# TopLevel.net
KiCad netlist of a schematic drawn in Altium Designer
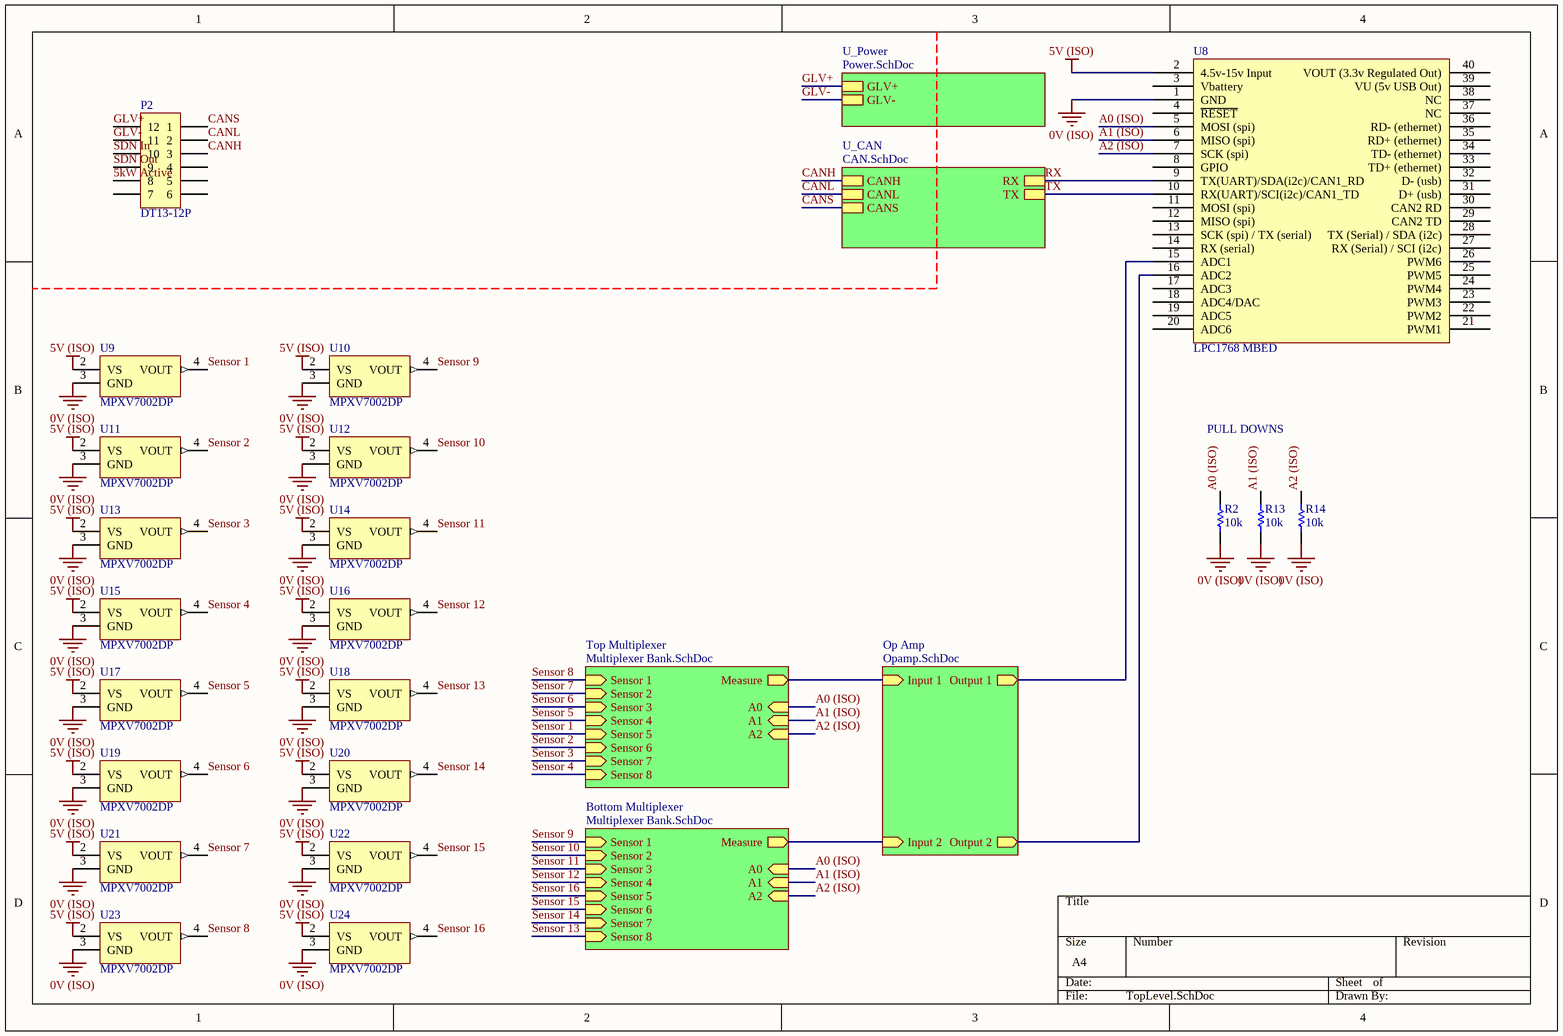
[diagram p0: TopLevel.SchDoc]

(export (version "E")
  (design (tool "Eeschema 10.0.6"))
  (components
    (comp (ref "P2")
      (value "DT13-12P")
      (footprint "DT13-12P")
      (fields (field (name "DIGIKEY PART NUMBER") "1734-1451-ND") (field (name "CONTACT") "Nickel"))
      (libsource (lib "ts_19-standard-connectors") (part "DT13-12P"))
    )
    (comp (ref "R2")
      (value "10k")
      (footprint "0805")
      (fields
        (field (name "MANUFACTURER") "YAGEO")
        (field (name "PART NUMBER") "RC0805FR0710KL")
        (field (name "TOLERANCE") "0.01")
      )
      (libsource (lib "ts_19-standard-library") (part "Resistor"))
    )
    (comp (ref "R13")
      (value "10k")
      (footprint "0805")
      (fields
        (field (name "MANUFACTURER") "YAGEO")
        (field (name "PART NUMBER") "RC0805FR0710KL")
        (field (name "TOLERANCE") "0.01")
      )
      (libsource (lib "ts_19-standard-library") (part "Resistor"))
    )
    (comp (ref "R14")
      (value "10k")
      (footprint "0805")
      (fields
        (field (name "MANUFACTURER") "YAGEO")
        (field (name "PART NUMBER") "RC0805FR0710KL")
        (field (name "TOLERANCE") "0.01")
      )
      (libsource (lib "ts_19-standard-library") (part "Resistor"))
    )
    (comp (ref "U8")
      (value "LPC1768 MBED")
      (footprint "LPC1768 MBED")
      (description "ARM M3 mBed Enabled Microcontroller")
      (fields (field (name "MANUFACTURER") "NXP") (field (name "DIGIKEY PART NUMBER") "568-4916-ND"))
      (libsource (lib "ts_19-standard-library") (part "LPC1768 MBED"))
    )
    (comp (ref "U9")
      (value "MPXV7002DP")
      (footprint "NXP 8-SOP")
      (fields (field (name "MANUFACTURER") "NXP") (field (name "DIGIKEY PART NUMBER") "MPXV7002DP-ND"))
      (libsource (lib "ts_19-standard-library") (part "MPXV7002DP"))
    )
    (comp (ref "U10")
      (value "MPXV7002DP")
      (footprint "NXP 8-SOP")
      (fields (field (name "MANUFACTURER") "NXP") (field (name "DIGIKEY PART NUMBER") "MPXV7002DP-ND"))
      (libsource (lib "ts_19-standard-library") (part "MPXV7002DP"))
    )
    (comp (ref "U11")
      (value "MPXV7002DP")
      (footprint "NXP 8-SOP")
      (fields (field (name "MANUFACTURER") "NXP") (field (name "DIGIKEY PART NUMBER") "MPXV7002DP-ND"))
      (libsource (lib "ts_19-standard-library") (part "MPXV7002DP"))
    )
    (comp (ref "U12")
      (value "MPXV7002DP")
      (footprint "NXP 8-SOP")
      (fields (field (name "MANUFACTURER") "NXP") (field (name "DIGIKEY PART NUMBER") "MPXV7002DP-ND"))
      (libsource (lib "ts_19-standard-library") (part "MPXV7002DP"))
    )
    (comp (ref "U13")
      (value "MPXV7002DP")
      (footprint "NXP 8-SOP")
      (fields (field (name "MANUFACTURER") "NXP") (field (name "DIGIKEY PART NUMBER") "MPXV7002DP-ND"))
      (libsource (lib "ts_19-standard-library") (part "MPXV7002DP"))
    )
    (comp (ref "U14")
      (value "MPXV7002DP")
      (footprint "NXP 8-SOP")
      (fields (field (name "MANUFACTURER") "NXP") (field (name "DIGIKEY PART NUMBER") "MPXV7002DP-ND"))
      (libsource (lib "ts_19-standard-library") (part "MPXV7002DP"))
    )
    (comp (ref "U15")
      (value "MPXV7002DP")
      (footprint "NXP 8-SOP")
      (fields (field (name "MANUFACTURER") "NXP") (field (name "DIGIKEY PART NUMBER") "MPXV7002DP-ND"))
      (libsource (lib "ts_19-standard-library") (part "MPXV7002DP"))
    )
    (comp (ref "U16")
      (value "MPXV7002DP")
      (footprint "NXP 8-SOP")
      (fields (field (name "MANUFACTURER") "NXP") (field (name "DIGIKEY PART NUMBER") "MPXV7002DP-ND"))
      (libsource (lib "ts_19-standard-library") (part "MPXV7002DP"))
    )
    (comp (ref "U17")
      (value "MPXV7002DP")
      (footprint "NXP 8-SOP")
      (fields (field (name "MANUFACTURER") "NXP") (field (name "DIGIKEY PART NUMBER") "MPXV7002DP-ND"))
      (libsource (lib "ts_19-standard-library") (part "MPXV7002DP"))
    )
    (comp (ref "U18")
      (value "MPXV7002DP")
      (footprint "NXP 8-SOP")
      (fields (field (name "MANUFACTURER") "NXP") (field (name "DIGIKEY PART NUMBER") "MPXV7002DP-ND"))
      (libsource (lib "ts_19-standard-library") (part "MPXV7002DP"))
    )
    (comp (ref "U19")
      (value "MPXV7002DP")
      (footprint "NXP 8-SOP")
      (fields (field (name "MANUFACTURER") "NXP") (field (name "DIGIKEY PART NUMBER") "MPXV7002DP-ND"))
      (libsource (lib "ts_19-standard-library") (part "MPXV7002DP"))
    )
    (comp (ref "U20")
      (value "MPXV7002DP")
      (footprint "NXP 8-SOP")
      (fields (field (name "MANUFACTURER") "NXP") (field (name "DIGIKEY PART NUMBER") "MPXV7002DP-ND"))
      (libsource (lib "ts_19-standard-library") (part "MPXV7002DP"))
    )
    (comp (ref "U21")
      (value "MPXV7002DP")
      (footprint "NXP 8-SOP")
      (fields (field (name "MANUFACTURER") "NXP") (field (name "DIGIKEY PART NUMBER") "MPXV7002DP-ND"))
      (libsource (lib "ts_19-standard-library") (part "MPXV7002DP"))
    )
    (comp (ref "U22")
      (value "MPXV7002DP")
      (footprint "NXP 8-SOP")
      (fields (field (name "MANUFACTURER") "NXP") (field (name "DIGIKEY PART NUMBER") "MPXV7002DP-ND"))
      (libsource (lib "ts_19-standard-library") (part "MPXV7002DP"))
    )
    (comp (ref "U23")
      (value "MPXV7002DP")
      (footprint "NXP 8-SOP")
      (fields (field (name "MANUFACTURER") "NXP") (field (name "DIGIKEY PART NUMBER") "MPXV7002DP-ND"))
      (libsource (lib "ts_19-standard-library") (part "MPXV7002DP"))
    )
    (comp (ref "U24")
      (value "MPXV7002DP")
      (footprint "NXP 8-SOP")
      (fields (field (name "MANUFACTURER") "NXP") (field (name "DIGIKEY PART NUMBER") "MPXV7002DP-ND"))
      (libsource (lib "ts_19-standard-library") (part "MPXV7002DP"))
    )
  )
  (nets
    (net (code "1") (name "/5kW Active") (class "Default")
      (node (ref "P2") (pin "8") (pinfunction "8_8") (pintype "passive"))
    )
    (net (code "2") (name "/A0 (ISO)") (class "Default")
      (node (ref "R2") (pin "2") (pinfunction "2_2") (pintype "passive"))
      (node (ref "U8") (pin "5") (pinfunction "MOSI_(spi)_5") (pintype "passive"))
    )
    (net (code "3") (name "/A1 (ISO)") (class "Default")
      (node (ref "R13") (pin "2") (pinfunction "2_2") (pintype "passive"))
      (node (ref "U8") (pin "6") (pinfunction "MISO_(spi)_6") (pintype "passive"))
    )
    (net (code "4") (name "/A2 (ISO)") (class "Default")
      (node (ref "R14") (pin "2") (pinfunction "2_2") (pintype "passive"))
      (node (ref "U8") (pin "7") (pinfunction "SCK_(spi)_7") (pintype "passive"))
    )
    (net (code "5") (name "/CANH") (class "Default")
      (node (ref "P2") (pin "3") (pinfunction "3_3") (pintype "power_in"))
    )
    (net (code "6") (name "/CANL") (class "Default")
      (node (ref "P2") (pin "2") (pinfunction "2_2") (pintype "power_in"))
    )
    (net (code "7") (name "/CANS") (class "Default")
      (node (ref "P2") (pin "1") (pinfunction "1_1") (pintype "power_in"))
    )
    (net (code "8") (name "/GLV+") (class "Default")
      (node (ref "P2") (pin "12") (pinfunction "12_12") (pintype "passive"))
    )
    (net (code "9") (name "/GLV-") (class "Default")
      (node (ref "P2") (pin "11") (pinfunction "11_11") (pintype "passive"))
    )
    (net (code "12") (name "/Output 1") (class "Default")
      (node (ref "U8") (pin "15") (pinfunction "ADC1_15") (pintype "passive"))
    )
    (net (code "13") (name "/Output 2") (class "Default")
      (node (ref "U8") (pin "16") (pinfunction "ADC2_16") (pintype "passive"))
    )
    (net (code "14") (name "/RX") (class "Default")
      (node (ref "U8") (pin "9") (pinfunction "TX(UART)/SDA(i2c)/CAN1_RD_9") (pintype "passive"))
    )
    (net (code "15") (name "/SDN In") (class "Default")
      (node (ref "P2") (pin "10") (pinfunction "10_10") (pintype "passive"))
    )
    (net (code "16") (name "/SDN Out") (class "Default")
      (node (ref "P2") (pin "9") (pinfunction "9_9") (pintype "passive"))
    )
    (net (code "17") (name "/Sensor 1") (class "Default")
      (node (ref "U9") (pin "4") (pinfunction "VOUT_4") (pintype "output"))
    )
    (net (code "18") (name "/Sensor 2") (class "Default")
      (node (ref "U11") (pin "4") (pinfunction "VOUT_4") (pintype "output"))
    )
    (net (code "19") (name "/Sensor 3") (class "Default")
      (node (ref "U13") (pin "4") (pinfunction "VOUT_4") (pintype "output"))
    )
    (net (code "20") (name "/Sensor 4") (class "Default")
      (node (ref "U15") (pin "4") (pinfunction "VOUT_4") (pintype "output"))
    )
    (net (code "21") (name "/Sensor 5") (class "Default")
      (node (ref "U17") (pin "4") (pinfunction "VOUT_4") (pintype "output"))
    )
    (net (code "22") (name "/Sensor 6") (class "Default")
      (node (ref "U19") (pin "4") (pinfunction "VOUT_4") (pintype "output"))
    )
    (net (code "23") (name "/Sensor 7") (class "Default")
      (node (ref "U21") (pin "4") (pinfunction "VOUT_4") (pintype "output"))
    )
    (net (code "24") (name "/Sensor 8") (class "Default")
      (node (ref "U23") (pin "4") (pinfunction "VOUT_4") (pintype "output"))
    )
    (net (code "25") (name "/Sensor 9") (class "Default")
      (node (ref "U10") (pin "4") (pinfunction "VOUT_4") (pintype "output"))
    )
    (net (code "26") (name "/Sensor 10") (class "Default")
      (node (ref "U12") (pin "4") (pinfunction "VOUT_4") (pintype "output"))
    )
    (net (code "27") (name "/Sensor 11") (class "Default")
      (node (ref "U14") (pin "4") (pinfunction "VOUT_4") (pintype "output"))
    )
    (net (code "28") (name "/Sensor 12") (class "Default")
      (node (ref "U16") (pin "4") (pinfunction "VOUT_4") (pintype "output"))
    )
    (net (code "29") (name "/Sensor 13") (class "Default")
      (node (ref "U18") (pin "4") (pinfunction "VOUT_4") (pintype "output"))
    )
    (net (code "30") (name "/Sensor 14") (class "Default")
      (node (ref "U20") (pin "4") (pinfunction "VOUT_4") (pintype "output"))
    )
    (net (code "31") (name "/Sensor 15") (class "Default")
      (node (ref "U22") (pin "4") (pinfunction "VOUT_4") (pintype "output"))
    )
    (net (code "32") (name "/Sensor 16") (class "Default")
      (node (ref "U24") (pin "4") (pinfunction "VOUT_4") (pintype "output"))
    )
    (net (code "33") (name "/TX") (class "Default")
      (node (ref "U8") (pin "10") (pinfunction "RX(UART)/SCI(i2c)/CAN1_TD_10") (pintype "passive"))
    )
    (net (code "34") (name "0V (ISO)") (class "Default")
      (node (ref "R13") (pin "1") (pinfunction "1_1") (pintype "passive"))
      (node (ref "R14") (pin "1") (pinfunction "1_1") (pintype "passive"))
      (node (ref "R2") (pin "1") (pinfunction "1_1") (pintype "passive"))
      (node (ref "U10") (pin "3") (pinfunction "GND_3") (pintype "power_in"))
      (node (ref "U11") (pin "3") (pinfunction "GND_3") (pintype "power_in"))
      (node (ref "U12") (pin "3") (pinfunction "GND_3") (pintype "power_in"))
      (node (ref "U13") (pin "3") (pinfunction "GND_3") (pintype "power_in"))
      (node (ref "U14") (pin "3") (pinfunction "GND_3") (pintype "power_in"))
      (node (ref "U15") (pin "3") (pinfunction "GND_3") (pintype "power_in"))
      (node (ref "U16") (pin "3") (pinfunction "GND_3") (pintype "power_in"))
      (node (ref "U17") (pin "3") (pinfunction "GND_3") (pintype "power_in"))
      (node (ref "U18") (pin "3") (pinfunction "GND_3") (pintype "power_in"))
      (node (ref "U19") (pin "3") (pinfunction "GND_3") (pintype "power_in"))
      (node (ref "U20") (pin "3") (pinfunction "GND_3") (pintype "power_in"))
      (node (ref "U21") (pin "3") (pinfunction "GND_3") (pintype "power_in"))
      (node (ref "U22") (pin "3") (pinfunction "GND_3") (pintype "power_in"))
      (node (ref "U23") (pin "3") (pinfunction "GND_3") (pintype "power_in"))
      (node (ref "U24") (pin "3") (pinfunction "GND_3") (pintype "power_in"))
      (node (ref "U8") (pin "1") (pinfunction "GND_1") (pintype "passive"))
      (node (ref "U9") (pin "3") (pinfunction "GND_3") (pintype "power_in"))
    )
    (net (code "35") (name "5V (ISO)") (class "Default")
      (node (ref "U10") (pin "2") (pinfunction "VS_2") (pintype "power_in"))
      (node (ref "U11") (pin "2") (pinfunction "VS_2") (pintype "power_in"))
      (node (ref "U12") (pin "2") (pinfunction "VS_2") (pintype "power_in"))
      (node (ref "U13") (pin "2") (pinfunction "VS_2") (pintype "power_in"))
      (node (ref "U14") (pin "2") (pinfunction "VS_2") (pintype "power_in"))
      (node (ref "U15") (pin "2") (pinfunction "VS_2") (pintype "power_in"))
      (node (ref "U16") (pin "2") (pinfunction "VS_2") (pintype "power_in"))
      (node (ref "U17") (pin "2") (pinfunction "VS_2") (pintype "power_in"))
      (node (ref "U18") (pin "2") (pinfunction "VS_2") (pintype "power_in"))
      (node (ref "U19") (pin "2") (pinfunction "VS_2") (pintype "power_in"))
      (node (ref "U20") (pin "2") (pinfunction "VS_2") (pintype "power_in"))
      (node (ref "U21") (pin "2") (pinfunction "VS_2") (pintype "power_in"))
      (node (ref "U22") (pin "2") (pinfunction "VS_2") (pintype "power_in"))
      (node (ref "U23") (pin "2") (pinfunction "VS_2") (pintype "power_in"))
      (node (ref "U24") (pin "2") (pinfunction "VS_2") (pintype "power_in"))
      (node (ref "U8") (pin "2") (pinfunction "4.5v-15v_Input_2") (pintype "passive"))
      (node (ref "U9") (pin "2") (pinfunction "VS_2") (pintype "power_in"))
    )
    (net (code "36") (name "unconnected-(P2-Pad4)") (class "Default")
      (node (ref "P2") (pin "4") (pinfunction "4_4") (pintype "power_in"))
    )
    (net (code "37") (name "unconnected-(P2-Pad5)") (class "Default")
      (node (ref "P2") (pin "5") (pinfunction "5_5") (pintype "power_in"))
    )
    (net (code "38") (name "unconnected-(P2-Pad6)") (class "Default")
      (node (ref "P2") (pin "6") (pinfunction "6_6") (pintype "power_in"))
    )
    (net (code "39") (name "unconnected-(P2-Pad7)") (class "Default")
      (node (ref "P2") (pin "7") (pinfunction "7_7") (pintype "passive"))
    )
    (net (code "40") (name "unconnected-(U8-ADC3-Pad17)") (class "Default")
      (node (ref "U8") (pin "17") (pinfunction "ADC3_17") (pintype "passive"))
    )
    (net (code "41") (name "unconnected-(U8-ADC4{slash}DAC-Pad18)") (class "Default")
      (node (ref "U8") (pin "18") (pinfunction "ADC4/DAC_18") (pintype "passive"))
    )
    (net (code "42") (name "unconnected-(U8-ADC5-Pad19)") (class "Default")
      (node (ref "U8") (pin "19") (pinfunction "ADC5_19") (pintype "passive"))
    )
    (net (code "43") (name "unconnected-(U8-ADC6-Pad20)") (class "Default")
      (node (ref "U8") (pin "20") (pinfunction "ADC6_20") (pintype "passive"))
    )
    (net (code "44") (name "unconnected-(U8-CAN2_RD-Pad30)") (class "Default")
      (node (ref "U8") (pin "30") (pinfunction "CAN2_RD_30") (pintype "passive"))
    )
    (net (code "45") (name "unconnected-(U8-CAN2_TD-Pad29)") (class "Default")
      (node (ref "U8") (pin "29") (pinfunction "CAN2_TD_29") (pintype "passive"))
    )
    (net (code "46") (name "unconnected-(U8-D+_(usb)-Pad31)") (class "Default")
      (node (ref "U8") (pin "31") (pinfunction "D+_(usb)_31") (pintype "passive"))
    )
    (net (code "47") (name "unconnected-(U8-D-_(usb)-Pad32)") (class "Default")
      (node (ref "U8") (pin "32") (pinfunction "D-_(usb)_32") (pintype "passive"))
    )
    (net (code "48") (name "unconnected-(U8-GPIO-Pad8)") (class "Default")
      (node (ref "U8") (pin "8") (pinfunction "GPIO_8") (pintype "passive"))
    )
    (net (code "49") (name "unconnected-(U8-MISO_(spi)-Pad12)") (class "Default")
      (node (ref "U8") (pin "12") (pinfunction "MISO_(spi)_12") (pintype "passive"))
    )
    (net (code "50") (name "unconnected-(U8-MOSI_(spi)-Pad11)") (class "Default")
      (node (ref "U8") (pin "11") (pinfunction "MOSI_(spi)_11") (pintype "passive"))
    )
    (net (code "51") (name "unconnected-(U8-NC-Pad37)") (class "Default")
      (node (ref "U8") (pin "37") (pinfunction "NC_37") (pintype "passive"))
    )
    (net (code "52") (name "unconnected-(U8-NC-Pad38)") (class "Default")
      (node (ref "U8") (pin "38") (pinfunction "NC_38") (pintype "passive"))
    )
    (net (code "53") (name "unconnected-(U8-PWM1-Pad21)") (class "Default")
      (node (ref "U8") (pin "21") (pinfunction "PWM1_21") (pintype "passive"))
    )
    (net (code "54") (name "unconnected-(U8-PWM2-Pad22)") (class "Default")
      (node (ref "U8") (pin "22") (pinfunction "PWM2_22") (pintype "passive"))
    )
    (net (code "55") (name "unconnected-(U8-PWM3-Pad23)") (class "Default")
      (node (ref "U8") (pin "23") (pinfunction "PWM3_23") (pintype "passive"))
    )
    (net (code "56") (name "unconnected-(U8-PWM4-Pad24)") (class "Default")
      (node (ref "U8") (pin "24") (pinfunction "PWM4_24") (pintype "passive"))
    )
    (net (code "57") (name "unconnected-(U8-PWM5-Pad25)") (class "Default")
      (node (ref "U8") (pin "25") (pinfunction "PWM5_25") (pintype "passive"))
    )
    (net (code "58") (name "unconnected-(U8-PWM6-Pad26)") (class "Default")
      (node (ref "U8") (pin "26") (pinfunction "PWM6_26") (pintype "passive"))
    )
    (net (code "59") (name "unconnected-(U8-RD+_(ethernet)-Pad35)") (class "Default")
      (node (ref "U8") (pin "35") (pinfunction "RD+_(ethernet)_35") (pintype "passive"))
    )
    (net (code "60") (name "unconnected-(U8-RD-_(ethernet)-Pad36)") (class "Default")
      (node (ref "U8") (pin "36") (pinfunction "RD-_(ethernet)_36") (pintype "passive"))
    )
    (net (code "61") (name "unconnected-(U8-RX_(Serial)_{slash}_SCI_(i2c)-Pad27)") (class "Default")
      (node (ref "U8") (pin "27") (pinfunction "RX_(Serial)_/_SCI_(i2c)_27") (pintype "passive"))
    )
    (net (code "62") (name "unconnected-(U8-RX_(serial)-Pad14)") (class "Default")
      (node (ref "U8") (pin "14") (pinfunction "RX_(serial)_14") (pintype "passive"))
    )
    (net (code "63") (name "unconnected-(U8-SCK_(spi)_{slash}_TX_(serial)-Pad13)") (class "Default")
      (node (ref "U8") (pin "13") (pinfunction "SCK_(spi)_/_TX_(serial)_13") (pintype "passive"))
    )
    (net (code "64") (name "unconnected-(U8-TD+_(ethernet)-Pad33)") (class "Default")
      (node (ref "U8") (pin "33") (pinfunction "TD+_(ethernet)_33") (pintype "passive"))
    )
    (net (code "65") (name "unconnected-(U8-TD-_(ethernet)-Pad34)") (class "Default")
      (node (ref "U8") (pin "34") (pinfunction "TD-_(ethernet)_34") (pintype "passive"))
    )
    (net (code "66") (name "unconnected-(U8-TX_(Serial)_{slash}_SDA_(i2c)-Pad28)") (class "Default")
      (node (ref "U8") (pin "28") (pinfunction "TX_(Serial)_/_SDA_(i2c)_28") (pintype "passive"))
    )
    (net (code "67") (name "unconnected-(U8-VOUT_(3.3v_Regulated_Out)-Pad40)") (class "Default")
      (node (ref "U8") (pin "40") (pinfunction "VOUT_(3.3v_Regulated_Out)_40") (pintype "passive"))
    )
    (net (code "68") (name "unconnected-(U8-VU_(5v_USB_Out)-Pad39)") (class "Default")
      (node (ref "U8") (pin "39") (pinfunction "VU_(5v_USB_Out)_39") (pintype "passive"))
    )
    (net (code "69") (name "unconnected-(U8-Vbattery-Pad3)") (class "Default")
      (node (ref "U8") (pin "3") (pinfunction "Vbattery_3") (pintype "passive"))
    )
    (net (code "70") (name "unconnected-(U8-~{RESET}-Pad4)") (class "Default")
      (node (ref "U8") (pin "4") (pinfunction "~{RESET}_4") (pintype "passive"))
    )
  )
)
